# AD.net
KiCad netlist of a schematic drawn in Altium Designer
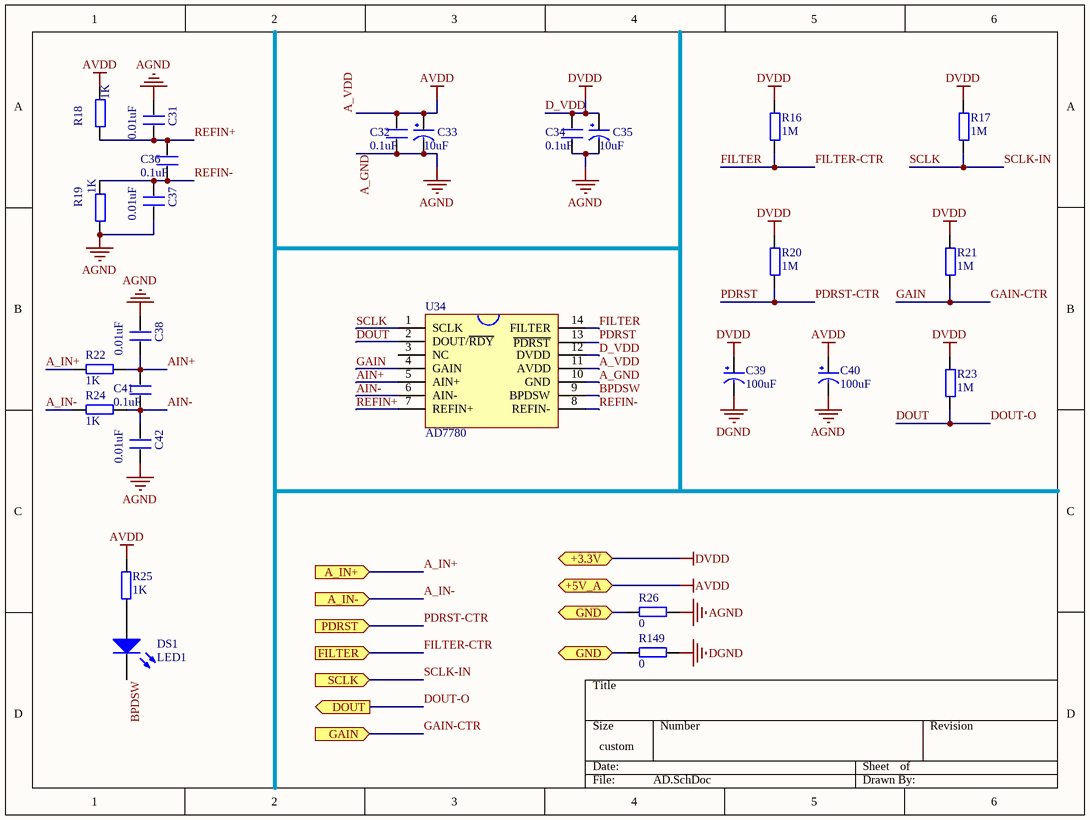
[diagram p0: AD.SchDoc]

(export (version "E")
  (design (tool "Eeschema 10.0.6"))
  (components
    (comp (ref "C31") (value "0.01uF") (footprint "0603P") (libsource (lib "MiniSTM32 V3.0封装库") (part "C")))
    (comp (ref "C32") (value "0.1uF") (footprint "0603P") (libsource (lib "MiniSTM32 V3.0封装库") (part "C")))
    (comp (ref "C33")
      (value "10uF")
      (footprint "CC6.56.5")
      (libsource (lib "MiniSTM32 V3.0封装库") (part "CAP"))
    )
    (comp (ref "C34") (value "0.1uF") (footprint "0603P") (libsource (lib "MiniSTM32 V3.0封装库") (part "C")))
    (comp (ref "C35")
      (value "10uF")
      (footprint "CC6.56.5")
      (libsource (lib "MiniSTM32 V3.0封装库") (part "CAP"))
    )
    (comp (ref "C36") (value "0.1uF") (footprint "0603P") (libsource (lib "MiniSTM32 V3.0封装库") (part "C")))
    (comp (ref "C37") (value "0.01uF") (footprint "0603P") (libsource (lib "MiniSTM32 V3.0封装库") (part "C")))
    (comp (ref "C38") (value "0.01uF") (footprint "0603P") (libsource (lib "MiniSTM32 V3.0封装库") (part "C")))
    (comp (ref "C39")
      (value "100uF")
      (footprint "CC6.56.5")
      (libsource (lib "MiniSTM32 V3.0封装库") (part "CAP"))
    )
    (comp (ref "C40")
      (value "100uF")
      (footprint "CC6.56.5")
      (libsource (lib "MiniSTM32 V3.0封装库") (part "CAP"))
    )
    (comp (ref "C41") (value "0.1uF") (footprint "0603P") (libsource (lib "MiniSTM32 V3.0封装库") (part "C")))
    (comp (ref "C42") (value "0.01uF") (footprint "0603P") (libsource (lib "MiniSTM32 V3.0封装库") (part "C")))
    (comp (ref "DS1")
      (value "LED1")
      (footprint "SMDLED")
      (description "Typical RED, GREEN, YELLOW, AMBER GaAs LED")
      (fields (field (name "PUBLISHER") "Altium Limited"))
      (libsource (lib "MiniSTM32 V3.0封装库") (part "LED2"))
    )
    (comp (ref "R16") (value "1M") (footprint "0603P") (libsource (lib "MiniSTM32 V3.0封装库") (part "R")))
    (comp (ref "R17") (value "1M") (footprint "0603P") (libsource (lib "MiniSTM32 V3.0封装库") (part "R")))
    (comp (ref "R18") (value "1K") (footprint "0603P") (libsource (lib "MiniSTM32 V3.0封装库") (part "R")))
    (comp (ref "R19") (value "1K") (footprint "0603P") (libsource (lib "MiniSTM32 V3.0封装库") (part "R")))
    (comp (ref "R20") (value "1M") (footprint "0603P") (libsource (lib "MiniSTM32 V3.0封装库") (part "R")))
    (comp (ref "R21") (value "1M") (footprint "0603P") (libsource (lib "MiniSTM32 V3.0封装库") (part "R")))
    (comp (ref "R22") (value "1K") (footprint "0603P") (libsource (lib "MiniSTM32 V3.0封装库") (part "R")))
    (comp (ref "R23") (value "1M") (footprint "0603P") (libsource (lib "MiniSTM32 V3.0封装库") (part "R")))
    (comp (ref "R24") (value "1K") (footprint "0603P") (libsource (lib "MiniSTM32 V3.0封装库") (part "R")))
    (comp (ref "R25") (value "1K") (footprint "0603P") (libsource (lib "MiniSTM32 V3.0封装库") (part "R")))
    (comp (ref "R26") (value "0") (footprint "0603P") (libsource (lib "MiniSTM32 V3.0封装库") (part "R")))
    (comp (ref "R149") (value "0") (footprint "0603P") (libsource (lib "MiniSTM32 V3.0封装库") (part "R")))
    (comp (ref "U34") (value "AD7780") (footprint "SOIC_14") (libsource (lib "dinafa") (part "AD7780")))
  )
  (nets
    (net (code "1") (name "/AIN+") (class "Default")
      (node (ref "C38") (pin "1") (pintype "passive"))
      (node (ref "C41") (pin "2") (pintype "passive"))
      (node (ref "R22") (pin "1") (pintype "passive"))
      (node (ref "U34") (pin "5") (pinfunction "AIN+_5") (pintype "passive"))
    )
    (net (code "2") (name "/AIN-") (class "Default")
      (node (ref "C41") (pin "1") (pintype "passive"))
      (node (ref "C42") (pin "2") (pintype "passive"))
      (node (ref "R24") (pin "1") (pintype "passive"))
      (node (ref "U34") (pin "6") (pinfunction "AIN-_6") (pintype "passive"))
    )
    (net (code "3") (name "/A_IN+") (class "Default") (node (ref "R22") (pin "2") (pintype "passive")))
    (net (code "4") (name "/A_IN-") (class "Default") (node (ref "R24") (pin "2") (pintype "passive")))
    (net (code "5") (name "/BPDSW") (class "Default")
      (node (ref "DS1") (pin "2") (pinfunction "K_2") (pintype "passive"))
      (node (ref "U34") (pin "9") (pinfunction "BPDSW_9") (pintype "passive"))
    )
    (net (code "6") (name "/DOUT") (class "Default")
      (node (ref "R23") (pin "1") (pintype "passive"))
      (node (ref "U34") (pin "2") (pinfunction "DOUT/~{RDY}_2") (pintype "passive"))
    )
    (net (code "7") (name "/FILTER") (class "Default")
      (node (ref "R16") (pin "1") (pintype "passive"))
      (node (ref "U34") (pin "14") (pinfunction "FILTER_14") (pintype "passive"))
    )
    (net (code "8") (name "/GAIN") (class "Default")
      (node (ref "R21") (pin "1") (pintype "passive"))
      (node (ref "U34") (pin "4") (pinfunction "GAIN_4") (pintype "passive"))
    )
    (net (code "9") (name "/GND") (class "Default")
      (node (ref "R149") (pin "2") (pintype "passive"))
      (node (ref "R26") (pin "2") (pintype "passive"))
    )
    (net (code "10") (name "/PDRST") (class "Default")
      (node (ref "R20") (pin "1") (pintype "passive"))
      (node (ref "U34") (pin "13") (pinfunction "~{PDRST}_13") (pintype "passive"))
    )
    (net (code "11") (name "/REFIN+") (class "Default")
      (node (ref "C31") (pin "1") (pintype "passive"))
      (node (ref "C36") (pin "2") (pintype "passive"))
      (node (ref "R18") (pin "1") (pintype "passive"))
      (node (ref "U34") (pin "7") (pinfunction "REFIN+_7") (pintype "passive"))
    )
    (net (code "12") (name "/REFIN-") (class "Default")
      (node (ref "C36") (pin "1") (pintype "passive"))
      (node (ref "C37") (pin "2") (pintype "passive"))
      (node (ref "R19") (pin "2") (pintype "passive"))
      (node (ref "U34") (pin "8") (pinfunction "REFIN-_8") (pintype "passive"))
    )
    (net (code "13") (name "/SCLK") (class "Default")
      (node (ref "R17") (pin "1") (pintype "passive"))
      (node (ref "U34") (pin "1") (pinfunction "SCLK_1") (pintype "passive"))
    )
    (net (code "14") (name "AGND") (class "Default")
      (node (ref "C31") (pin "2") (pintype "passive"))
      (node (ref "C32") (pin "1") (pintype "passive"))
      (node (ref "C33") (pin "2") (pinfunction "GND_2") (pintype "passive"))
      (node (ref "C34") (pin "1") (pintype "passive"))
      (node (ref "C35") (pin "2") (pinfunction "GND_2") (pintype "passive"))
      (node (ref "C37") (pin "1") (pintype "passive"))
      (node (ref "C38") (pin "2") (pintype "passive"))
      (node (ref "C40") (pin "2") (pinfunction "GND_2") (pintype "passive"))
      (node (ref "C42") (pin "1") (pintype "passive"))
      (node (ref "R19") (pin "1") (pintype "passive"))
      (node (ref "R26") (pin "1") (pintype "passive"))
      (node (ref "U34") (pin "10") (pinfunction "GND_10") (pintype "passive"))
    )
    (net (code "15") (name "AVDD") (class "Default")
      (node (ref "C32") (pin "2") (pintype "passive"))
      (node (ref "C33") (pin "1") (pinfunction "VCC_1") (pintype "passive"))
      (node (ref "C40") (pin "1") (pinfunction "VCC_1") (pintype "passive"))
      (node (ref "R18") (pin "2") (pintype "passive"))
      (node (ref "R25") (pin "1") (pintype "passive"))
      (node (ref "U34") (pin "11") (pinfunction "AVDD_11") (pintype "passive"))
    )
    (net (code "16") (name "DGND") (class "Default")
      (node (ref "C39") (pin "2") (pinfunction "GND_2") (pintype "passive"))
      (node (ref "R149") (pin "1") (pintype "passive"))
    )
    (net (code "17") (name "DVDD") (class "Default")
      (node (ref "C34") (pin "2") (pintype "passive"))
      (node (ref "C35") (pin "1") (pinfunction "VCC_1") (pintype "passive"))
      (node (ref "C39") (pin "1") (pinfunction "VCC_1") (pintype "passive"))
      (node (ref "R16") (pin "2") (pintype "passive"))
      (node (ref "R17") (pin "2") (pintype "passive"))
      (node (ref "R20") (pin "2") (pintype "passive"))
      (node (ref "R21") (pin "2") (pintype "passive"))
      (node (ref "R23") (pin "2") (pintype "passive"))
      (node (ref "U34") (pin "12") (pinfunction "DVDD_12") (pintype "passive"))
    )
    (net (code "18") (name "Net-(DS1-A)") (class "Default")
      (node (ref "DS1") (pin "1") (pinfunction "A_1") (pintype "passive"))
      (node (ref "R25") (pin "2") (pintype "passive"))
    )
    (net (code "19") (name "unconnected-(U34-NC-Pad3)") (class "Default")
      (node (ref "U34") (pin "3") (pinfunction "NC_3") (pintype "passive"))
    )
  )
)
